# XSensorAdapter.net
KiCad netlist of a schematic drawn in EAGLE
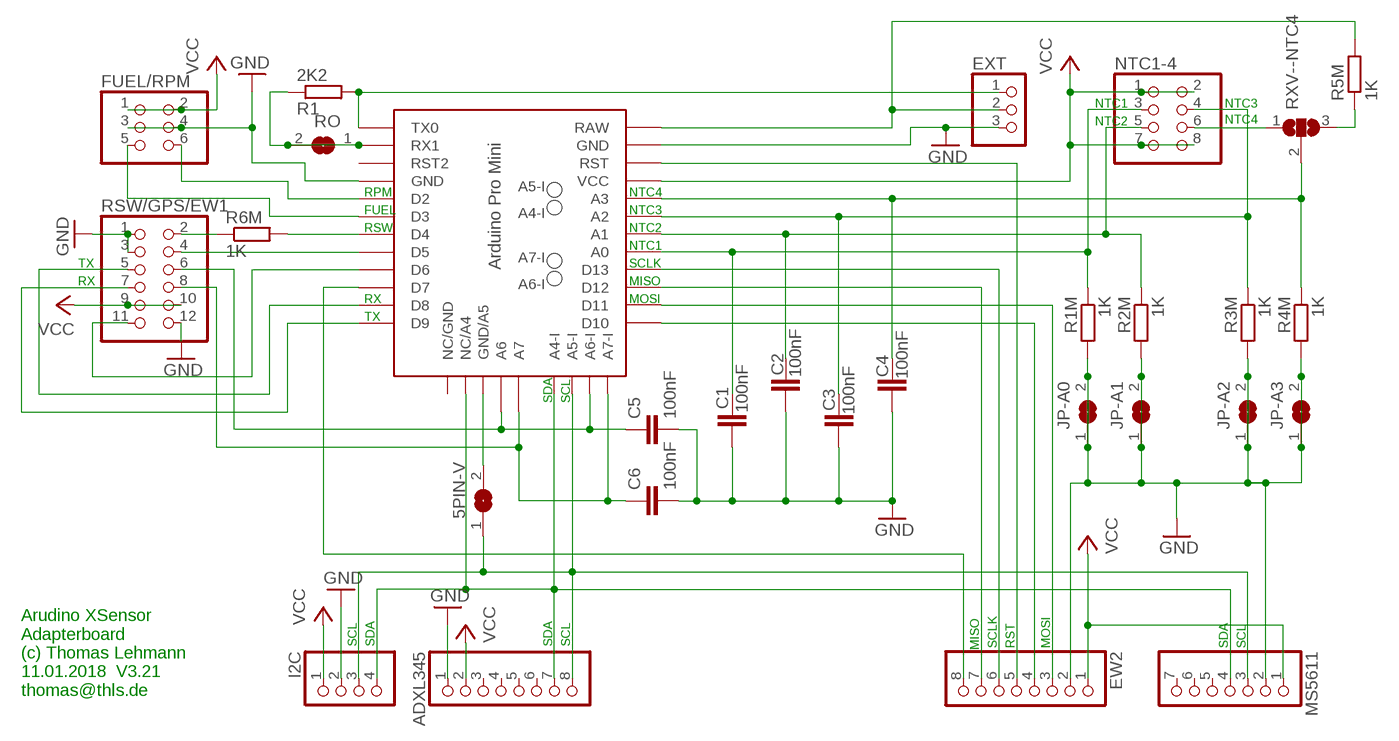
[diagram p0: schematic, sheet 1]

(export (version "E")
  (design (tool "Eeschema 10.0.6"))
  (components
    (comp (ref "5PIN-V")
      (value "SJ")
      (footprint "eagle-import:SJ")
      (libsource (lib "eagle-import") (part "SJ"))
    )
    (comp (ref "ADXL345")
      (value "PINHD-1X8")
      (footprint "eagle-import:1X08")
      (libsource (lib "eagle-import") (part "PINHD-1X8"))
    )
    (comp (ref "C1")
      (value "100nF")
      (footprint "eagle-import:C2.5-2")
      (libsource (lib "eagle-import") (part "C2.5/2"))
    )
    (comp (ref "C2")
      (value "100nF")
      (footprint "eagle-import:C2.5-2")
      (libsource (lib "eagle-import") (part "C2.5/2"))
    )
    (comp (ref "C3")
      (value "100nF")
      (footprint "eagle-import:C2.5-2")
      (libsource (lib "eagle-import") (part "C2.5/2"))
    )
    (comp (ref "C4")
      (value "100nF")
      (footprint "eagle-import:C2.5-2")
      (libsource (lib "eagle-import") (part "C2.5/2"))
    )
    (comp (ref "C5")
      (value "100nF")
      (footprint "eagle-import:C2.5-2")
      (libsource (lib "eagle-import") (part "C2.5/2"))
    )
    (comp (ref "C6")
      (value "100nF")
      (footprint "eagle-import:C2.5-2")
      (libsource (lib "eagle-import") (part "C2.5/2"))
    )
    (comp (ref "EW2")
      (value "PINHD-1X8")
      (footprint "eagle-import:1X08")
      (libsource (lib "eagle-import") (part "PINHD-1X8"))
    )
    (comp (ref "EXT")
      (value "PINHD-1X3")
      (footprint "eagle-import:1X03")
      (libsource (lib "eagle-import") (part "PINHD-1X3"))
    )
    (comp (ref "FUEL/RPM")
      (value "PINHD-2X3")
      (footprint "eagle-import:2X03")
      (libsource (lib "eagle-import") (part "PINHD-2X3"))
    )
    (comp (ref "I2C")
      (value "PINHD-1X4")
      (footprint "eagle-import:1X04")
      (libsource (lib "eagle-import") (part "PINHD-1X4"))
    )
    (comp (ref "JP-A0")
      (value "SJ")
      (footprint "eagle-import:SJ")
      (libsource (lib "eagle-import") (part "SJ"))
    )
    (comp (ref "JP-A1")
      (value "SJ")
      (footprint "eagle-import:SJ")
      (libsource (lib "eagle-import") (part "SJ"))
    )
    (comp (ref "JP-A2")
      (value "SJ")
      (footprint "eagle-import:SJ")
      (libsource (lib "eagle-import") (part "SJ"))
    )
    (comp (ref "JP-A3")
      (value "SJ")
      (footprint "eagle-import:SJ")
      (libsource (lib "eagle-import") (part "SJ"))
    )
    (comp (ref "MS5611")
      (value "PINHD-1X7")
      (footprint "eagle-import:1X07")
      (libsource (lib "eagle-import") (part "PINHD-1X7"))
    )
    (comp (ref "NTC1-4")
      (value "PINHD-2X4")
      (footprint "eagle-import:2X04")
      (libsource (lib "eagle-import") (part "PINHD-2X4"))
    )
    (comp (ref "R1")
      (value "2K2")
      (footprint "eagle-import:0207_10")
      (libsource (lib "eagle-import") (part "R-EU_0207/10"))
    )
    (comp (ref "R1M")
      (value "1K")
      (footprint "eagle-import:0207_10")
      (libsource (lib "eagle-import") (part "R-EU_0207/10"))
    )
    (comp (ref "R2M")
      (value "1K")
      (footprint "eagle-import:0207_10")
      (libsource (lib "eagle-import") (part "R-EU_0207/10"))
    )
    (comp (ref "R3M")
      (value "1K")
      (footprint "eagle-import:0207_10")
      (libsource (lib "eagle-import") (part "R-EU_0207/10"))
    )
    (comp (ref "R4M")
      (value "1K")
      (footprint "eagle-import:0207_10")
      (libsource (lib "eagle-import") (part "R-EU_0207/10"))
    )
    (comp (ref "R5M")
      (value "1K")
      (footprint "eagle-import:0207_10")
      (libsource (lib "eagle-import") (part "R-EU_0207/10"))
    )
    (comp (ref "R6M")
      (value "1K")
      (footprint "eagle-import:0207_10")
      (libsource (lib "eagle-import") (part "R-EU_0207/10"))
    )
    (comp (ref "RO") (value "SJ") (footprint "eagle-import:SJ") (libsource (lib "eagle-import") (part "SJ")))
    (comp (ref "RSW/GPS/EW1")
      (value "PINHD-2X6")
      (footprint "eagle-import:2X06")
      (libsource (lib "eagle-import") (part "PINHD-2X6"))
    )
    (comp (ref "RXV--NTC4")
      (value "SJ2W")
      (footprint "eagle-import:SJ_2")
      (libsource (lib "eagle-import") (part "SJ2W"))
    )
    (comp (ref "U$1")
      (value "PRO-MINI-5PINPRO-MINI-5PIN")
      (footprint "eagle-import:PRO-MINI-5PIN")
      (libsource (lib "eagle-import") (part "PRO-MINI-5PINPRO-MINI-5PIN"))
    )
  )
  (nets
    (net (code "1") (name "GND") (class "Default")
      (node (ref "ADXL345") (pin "1") (pinfunction "1_1") (pintype "passive"))
      (node (ref "C1") (pin "2") (pinfunction "2_2") (pintype "passive"))
      (node (ref "C2") (pin "2") (pinfunction "2_2") (pintype "passive"))
      (node (ref "C3") (pin "2") (pinfunction "2_2") (pintype "passive"))
      (node (ref "C4") (pin "2") (pinfunction "2_2") (pintype "passive"))
      (node (ref "C5") (pin "2") (pinfunction "2_2") (pintype "passive"))
      (node (ref "C6") (pin "2") (pinfunction "2_2") (pintype "passive"))
      (node (ref "EW2") (pin "2") (pinfunction "2_2") (pintype "passive"))
      (node (ref "EXT") (pin "3") (pinfunction "3_3") (pintype "passive"))
      (node (ref "FUEL/RPM") (pin "3") (pinfunction "3_3") (pintype "passive"))
      (node (ref "FUEL/RPM") (pin "4") (pinfunction "4_4") (pintype "passive"))
      (node (ref "I2C") (pin "2") (pinfunction "2_2") (pintype "passive"))
      (node (ref "JP-A0") (pin "1") (pinfunction "1_1") (pintype "passive"))
      (node (ref "JP-A0") (pin "2") (pinfunction "2_2") (pintype "passive"))
      (node (ref "JP-A1") (pin "1") (pinfunction "1_1") (pintype "passive"))
      (node (ref "JP-A1") (pin "2") (pinfunction "2_2") (pintype "passive"))
      (node (ref "JP-A2") (pin "1") (pinfunction "1_1") (pintype "passive"))
      (node (ref "JP-A2") (pin "2") (pinfunction "2_2") (pintype "passive"))
      (node (ref "JP-A3") (pin "1") (pinfunction "1_1") (pintype "passive"))
      (node (ref "JP-A3") (pin "2") (pinfunction "2_2") (pintype "passive"))
      (node (ref "MS5611") (pin "2") (pinfunction "2_2") (pintype "passive"))
      (node (ref "R1M") (pin "2") (pinfunction "2_2") (pintype "passive"))
      (node (ref "R2M") (pin "2") (pinfunction "2_2") (pintype "passive"))
      (node (ref "R3M") (pin "2") (pinfunction "2_2") (pintype "passive"))
      (node (ref "R4M") (pin "2") (pinfunction "2_2") (pintype "passive"))
      (node (ref "RSW/GPS/EW1") (pin "1") (pinfunction "1_1") (pintype "passive"))
      (node (ref "RSW/GPS/EW1") (pin "12") (pinfunction "12_12") (pintype "passive"))
      (node (ref "RSW/GPS/EW1") (pin "3") (pinfunction "3_3") (pintype "passive"))
      (node (ref "U$1") (pin "GND") (pinfunction "GND_GND") (pintype "power_in"))
      (node (ref "U$1") (pin "GND1") (pinfunction "GND_GND1") (pintype "power_in"))
    )
    (net (code "2") (name "Net-(5PIN-V-Pad1)") (class "Default")
      (node (ref "5PIN-V") (pin "1") (pinfunction "1_1") (pintype "passive"))
      (node (ref "ADXL345") (pin "8") (pinfunction "8_8") (pintype "passive"))
      (node (ref "I2C") (pin "3") (pinfunction "3_3") (pintype "passive"))
      (node (ref "MS5611") (pin "3") (pinfunction "3_3") (pintype "passive"))
      (node (ref "U$1") (pin "A5-I") (pinfunction "A5-I_A5-I") (pintype "bidirectional"))
    )
    (net (code "3") (name "Net-(5PIN-V-Pad2)") (class "Default")
      (node (ref "5PIN-V") (pin "2") (pinfunction "2_2") (pintype "passive"))
      (node (ref "U$1") (pin "GND/A5") (pinfunction "GND/A5_GND/A5") (pintype "bidirectional"))
    )
    (net (code "4") (name "Net-(ADXL345-Pad7)") (class "Default")
      (node (ref "ADXL345") (pin "7") (pinfunction "7_7") (pintype "passive"))
      (node (ref "I2C") (pin "4") (pinfunction "4_4") (pintype "passive"))
      (node (ref "MS5611") (pin "4") (pinfunction "4_4") (pintype "passive"))
      (node (ref "U$1") (pin "A4-I") (pinfunction "A4-I_A4-I") (pintype "bidirectional"))
      (node (ref "U$1") (pin "NC/A4") (pinfunction "NC/A4_NC/A4") (pintype "bidirectional"))
    )
    (net (code "5") (name "Net-(C1-Pad1)") (class "Default")
      (node (ref "C1") (pin "1") (pinfunction "1_1") (pintype "passive"))
      (node (ref "NTC1-4") (pin "3") (pinfunction "3_3") (pintype "passive"))
      (node (ref "R1M") (pin "1") (pinfunction "1_1") (pintype "passive"))
      (node (ref "U$1") (pin "A0") (pinfunction "A0_A0") (pintype "bidirectional"))
    )
    (net (code "6") (name "Net-(C2-Pad1)") (class "Default")
      (node (ref "C2") (pin "1") (pinfunction "1_1") (pintype "passive"))
      (node (ref "NTC1-4") (pin "5") (pinfunction "5_5") (pintype "passive"))
      (node (ref "R2M") (pin "1") (pinfunction "1_1") (pintype "passive"))
      (node (ref "U$1") (pin "A1") (pinfunction "A1_A1") (pintype "bidirectional"))
    )
    (net (code "7") (name "Net-(C3-Pad1)") (class "Default")
      (node (ref "C3") (pin "1") (pinfunction "1_1") (pintype "passive"))
      (node (ref "NTC1-4") (pin "4") (pinfunction "4_4") (pintype "passive"))
      (node (ref "R3M") (pin "1") (pinfunction "1_1") (pintype "passive"))
      (node (ref "U$1") (pin "A2") (pinfunction "A2_A2") (pintype "bidirectional"))
    )
    (net (code "8") (name "Net-(C4-Pad1)") (class "Default")
      (node (ref "C4") (pin "1") (pinfunction "1_1") (pintype "passive"))
      (node (ref "R4M") (pin "1") (pinfunction "1_1") (pintype "passive"))
      (node (ref "RXV--NTC4") (pin "2") (pinfunction "2_2") (pintype "passive"))
      (node (ref "U$1") (pin "A3") (pinfunction "A3_A3") (pintype "bidirectional"))
    )
    (net (code "9") (name "Net-(C5-Pad1)") (class "Default")
      (node (ref "C5") (pin "1") (pinfunction "1_1") (pintype "passive"))
      (node (ref "RSW/GPS/EW1") (pin "6") (pinfunction "6_6") (pintype "passive"))
      (node (ref "U$1") (pin "A6") (pinfunction "A6_A6") (pintype "bidirectional"))
      (node (ref "U$1") (pin "A6-I") (pinfunction "A6-I_A6-I") (pintype "bidirectional"))
    )
    (net (code "10") (name "Net-(C6-Pad1)") (class "Default")
      (node (ref "C6") (pin "1") (pinfunction "1_1") (pintype "passive"))
      (node (ref "RSW/GPS/EW1") (pin "8") (pinfunction "8_8") (pintype "passive"))
      (node (ref "U$1") (pin "A7") (pinfunction "A7_A7") (pintype "bidirectional"))
      (node (ref "U$1") (pin "A7-I") (pinfunction "A7-I_A7-I") (pintype "bidirectional"))
    )
    (net (code "11") (name "Net-(EW2-Pad3)") (class "Default")
      (node (ref "EW2") (pin "3") (pinfunction "3_3") (pintype "passive"))
      (node (ref "U$1") (pin "D11") (pinfunction "D11_D11") (pintype "bidirectional"))
    )
    (net (code "12") (name "Net-(EW2-Pad4)") (class "Default")
      (node (ref "EW2") (pin "4") (pinfunction "4_4") (pintype "passive"))
      (node (ref "U$1") (pin "D10") (pinfunction "D10_D10") (pintype "bidirectional"))
    )
    (net (code "13") (name "Net-(EW2-Pad5)") (class "Default")
      (node (ref "EW2") (pin "5") (pinfunction "5_5") (pintype "passive"))
      (node (ref "U$1") (pin "RST") (pinfunction "RST_RST") (pintype "bidirectional"))
    )
    (net (code "14") (name "Net-(EW2-Pad6)") (class "Default")
      (node (ref "EW2") (pin "6") (pinfunction "6_6") (pintype "passive"))
      (node (ref "U$1") (pin "D13") (pinfunction "D13_D13") (pintype "bidirectional"))
    )
    (net (code "15") (name "Net-(EW2-Pad7)") (class "Default")
      (node (ref "EW2") (pin "7") (pinfunction "7_7") (pintype "passive"))
      (node (ref "U$1") (pin "D12") (pinfunction "D12_D12") (pintype "bidirectional"))
    )
    (net (code "16") (name "Net-(EW2-Pad8)") (class "Default")
      (node (ref "EW2") (pin "8") (pinfunction "8_8") (pintype "passive"))
      (node (ref "U$1") (pin "D7") (pinfunction "D7_D7") (pintype "bidirectional"))
    )
    (net (code "17") (name "Net-(EXT-Pad1)") (class "Default")
      (node (ref "EXT") (pin "1") (pinfunction "1_1") (pintype "passive"))
      (node (ref "R1") (pin "2") (pinfunction "2_2") (pintype "passive"))
      (node (ref "U$1") (pin "TX0") (pinfunction "TX0_TX0") (pintype "bidirectional"))
    )
    (net (code "18") (name "Net-(EXT-Pad2)") (class "Default")
      (node (ref "EXT") (pin "2") (pinfunction "2_2") (pintype "passive"))
      (node (ref "R5M") (pin "2") (pinfunction "2_2") (pintype "passive"))
      (node (ref "U$1") (pin "RAW") (pinfunction "RAW_RAW") (pintype "bidirectional"))
    )
    (net (code "19") (name "Net-(FUEL/RPM-Pad5)") (class "Default")
      (node (ref "FUEL/RPM") (pin "5") (pinfunction "5_5") (pintype "passive"))
      (node (ref "U$1") (pin "D3") (pinfunction "D3_D3") (pintype "bidirectional"))
    )
    (net (code "20") (name "Net-(FUEL/RPM-Pad6)") (class "Default")
      (node (ref "FUEL/RPM") (pin "6") (pinfunction "6_6") (pintype "passive"))
      (node (ref "U$1") (pin "D2") (pinfunction "D2_D2") (pintype "bidirectional"))
    )
    (net (code "21") (name "Net-(NTC1-4-Pad6)") (class "Default")
      (node (ref "NTC1-4") (pin "6") (pinfunction "6_6") (pintype "passive"))
      (node (ref "RXV--NTC4") (pin "1") (pinfunction "1_1") (pintype "passive"))
    )
    (net (code "22") (name "Net-(R1-Pad1)") (class "Default")
      (node (ref "R1") (pin "1") (pinfunction "1_1") (pintype "passive"))
      (node (ref "RO") (pin "1") (pinfunction "1_1") (pintype "passive"))
      (node (ref "RO") (pin "2") (pinfunction "2_2") (pintype "passive"))
      (node (ref "U$1") (pin "RX1") (pinfunction "RX1_RX1") (pintype "bidirectional"))
    )
    (net (code "23") (name "Net-(R5M-Pad1)") (class "Default")
      (node (ref "R5M") (pin "1") (pinfunction "1_1") (pintype "passive"))
      (node (ref "RXV--NTC4") (pin "3") (pinfunction "3_3") (pintype "passive"))
    )
    (net (code "24") (name "Net-(R6M-Pad1)") (class "Default")
      (node (ref "R6M") (pin "1") (pinfunction "1_1") (pintype "passive"))
      (node (ref "RSW/GPS/EW1") (pin "2") (pinfunction "2_2") (pintype "passive"))
    )
    (net (code "25") (name "Net-(R6M-Pad2)") (class "Default")
      (node (ref "R6M") (pin "2") (pinfunction "2_2") (pintype "passive"))
      (node (ref "U$1") (pin "D4") (pinfunction "D4_D4") (pintype "bidirectional"))
    )
    (net (code "26") (name "Net-(RSW/GPS/EW1-Pad4)") (class "Default")
      (node (ref "RSW/GPS/EW1") (pin "4") (pinfunction "4_4") (pintype "passive"))
      (node (ref "U$1") (pin "D5") (pinfunction "D5_D5") (pintype "bidirectional"))
    )
    (net (code "27") (name "Net-(RSW/GPS/EW1-Pad5)") (class "Default")
      (node (ref "RSW/GPS/EW1") (pin "5") (pinfunction "5_5") (pintype "passive"))
      (node (ref "U$1") (pin "D8") (pinfunction "D8_D8") (pintype "bidirectional"))
    )
    (net (code "28") (name "Net-(RSW/GPS/EW1-Pad7)") (class "Default")
      (node (ref "RSW/GPS/EW1") (pin "7") (pinfunction "7_7") (pintype "passive"))
      (node (ref "U$1") (pin "D9") (pinfunction "D9_D9") (pintype "bidirectional"))
    )
    (net (code "29") (name "Net-(RSW/GPS/EW1-Pad11)") (class "Default")
      (node (ref "RSW/GPS/EW1") (pin "11") (pinfunction "11_11") (pintype "passive"))
      (node (ref "U$1") (pin "D6") (pinfunction "D6_D6") (pintype "bidirectional"))
    )
    (net (code "30") (name "VCC") (class "Default")
      (node (ref "ADXL345") (pin "2") (pinfunction "2_2") (pintype "passive"))
      (node (ref "EW2") (pin "1") (pinfunction "1_1") (pintype "passive"))
      (node (ref "FUEL/RPM") (pin "1") (pinfunction "1_1") (pintype "passive"))
      (node (ref "FUEL/RPM") (pin "2") (pinfunction "2_2") (pintype "passive"))
      (node (ref "I2C") (pin "1") (pinfunction "1_1") (pintype "passive"))
      (node (ref "MS5611") (pin "1") (pinfunction "1_1") (pintype "passive"))
      (node (ref "NTC1-4") (pin "1") (pinfunction "1_1") (pintype "passive"))
      (node (ref "NTC1-4") (pin "2") (pinfunction "2_2") (pintype "passive"))
      (node (ref "NTC1-4") (pin "7") (pinfunction "7_7") (pintype "passive"))
      (node (ref "NTC1-4") (pin "8") (pinfunction "8_8") (pintype "passive"))
      (node (ref "RSW/GPS/EW1") (pin "10") (pinfunction "10_10") (pintype "passive"))
      (node (ref "RSW/GPS/EW1") (pin "9") (pinfunction "9_9") (pintype "passive"))
      (node (ref "U$1") (pin "VCC") (pinfunction "VCC_VCC") (pintype "bidirectional"))
    )
    (net (code "31") (name "unconnected-(ADXL345-Pad3)") (class "Default")
      (node (ref "ADXL345") (pin "3") (pinfunction "3_3") (pintype "passive"))
    )
    (net (code "32") (name "unconnected-(ADXL345-Pad4)") (class "Default")
      (node (ref "ADXL345") (pin "4") (pinfunction "4_4") (pintype "passive"))
    )
    (net (code "33") (name "unconnected-(ADXL345-Pad5)") (class "Default")
      (node (ref "ADXL345") (pin "5") (pinfunction "5_5") (pintype "passive"))
    )
    (net (code "34") (name "unconnected-(ADXL345-Pad6)") (class "Default")
      (node (ref "ADXL345") (pin "6") (pinfunction "6_6") (pintype "passive"))
    )
    (net (code "35") (name "unconnected-(MS5611-Pad5)") (class "Default")
      (node (ref "MS5611") (pin "5") (pinfunction "5_5") (pintype "passive"))
    )
    (net (code "36") (name "unconnected-(MS5611-Pad6)") (class "Default")
      (node (ref "MS5611") (pin "6") (pinfunction "6_6") (pintype "passive"))
    )
    (net (code "37") (name "unconnected-(MS5611-Pad7)") (class "Default")
      (node (ref "MS5611") (pin "7") (pinfunction "7_7") (pintype "passive"))
    )
    (net (code "38") (name "unconnected-(U$1-PadNC{slash}GND)") (class "Default")
      (node (ref "U$1") (pin "NC/GND") (pinfunction "NC/GND_NC/GND") (pintype "no_connect"))
    )
    (net (code "39") (name "unconnected-(U$1-RST2-PadRST1)") (class "Default")
      (node (ref "U$1") (pin "RST1") (pinfunction "RST2_RST1") (pintype "bidirectional"))
    )
  )
)
